# module_S-RX28_rev06_644.net
KiCad netlist of a schematic drawn in EAGLE
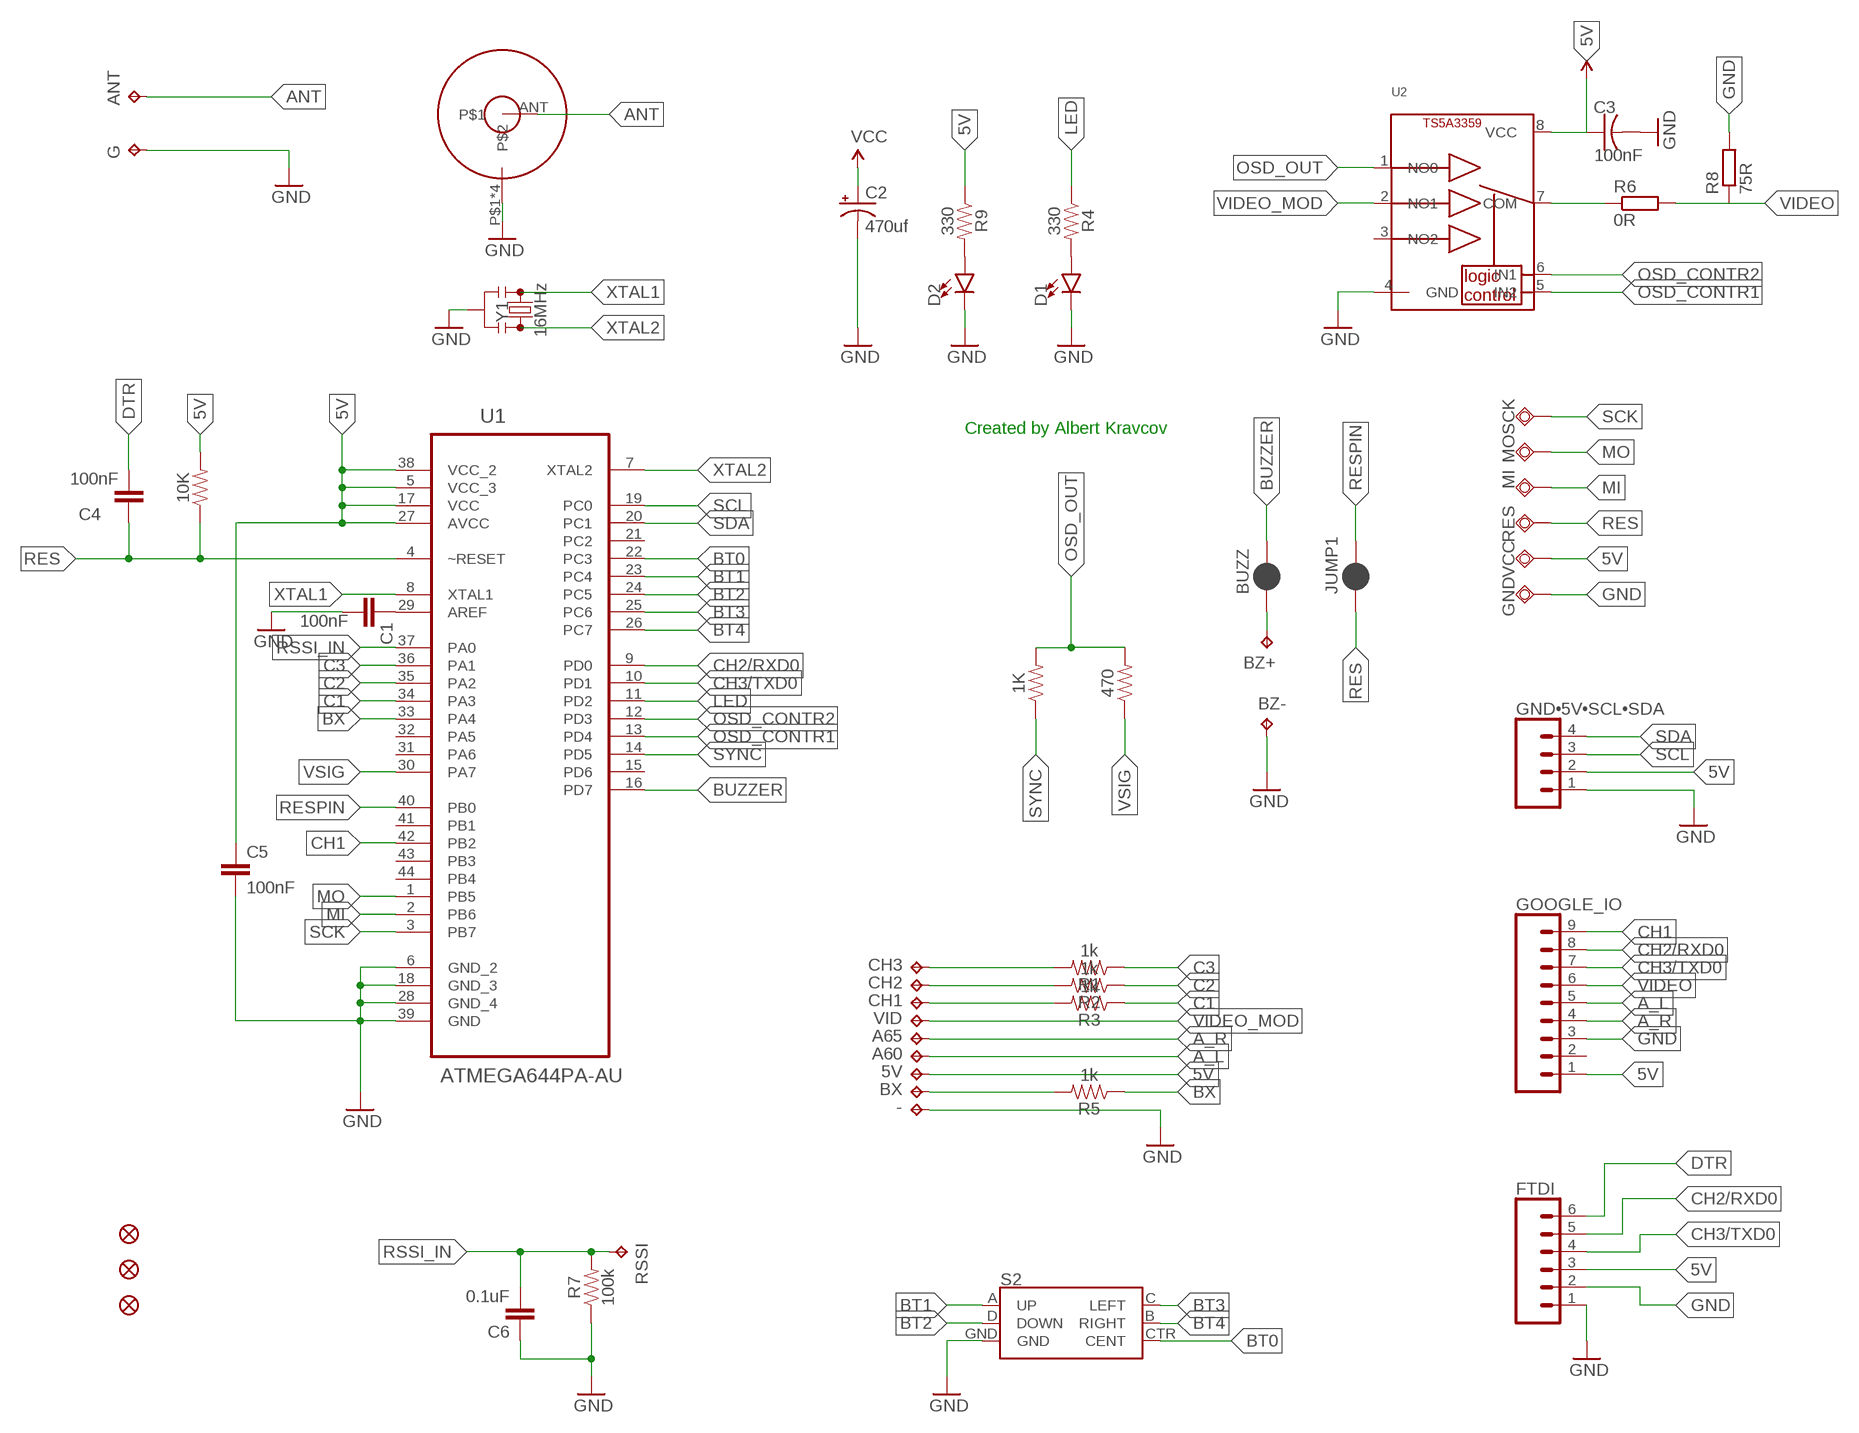
[diagram p0: schematic, sheet 1]

(export (version "E")
  (design (tool "Eeschema 10.0.6"))
  (components
    (comp (ref "-")
      (value "TPTP15SQ")
      (footprint "eagle-import:TP15SQ")
      (libsource (lib "eagle-import") (part "TPTP15SQ"))
    )
    (comp (ref "1K")
      (value "0.27OHM-0603-1/10W-1%")
      (footprint "eagle-import:0603")
      (libsource (lib "eagle-import") (part "0.27OHM-0603-1/10W-1%"))
    )
    (comp (ref "5V")
      (value "TPTP15SQ")
      (footprint "eagle-import:TP15SQ")
      (libsource (lib "eagle-import") (part "TPTP15SQ"))
    )
    (comp (ref "10K")
      (value "0.27OHM-0603-1/10W-1%")
      (footprint "eagle-import:0603")
      (libsource (lib "eagle-import") (part "0.27OHM-0603-1/10W-1%"))
    )
    (comp (ref "470")
      (value "0.27OHM-0603-1/10W-1%")
      (footprint "eagle-import:0603")
      (libsource (lib "eagle-import") (part "0.27OHM-0603-1/10W-1%"))
    )
    (comp (ref "A60")
      (value "TPTP15SQ")
      (footprint "eagle-import:TP15SQ")
      (libsource (lib "eagle-import") (part "TPTP15SQ"))
    )
    (comp (ref "A65")
      (value "TPTP15SQ")
      (footprint "eagle-import:TP15SQ")
      (libsource (lib "eagle-import") (part "TPTP15SQ"))
    )
    (comp (ref "ANT")
      (value "TPTP15R")
      (footprint "eagle-import:TP15R")
      (libsource (lib "eagle-import") (part "TPTP15R"))
    )
    (comp (ref "BUZZ")
      (value "JUMPER-SMT_2_NC_PASTE_SILK")
      (footprint "eagle-import:SMT-JUMPER_2_NC_PASTE_SILK")
      (libsource (lib "eagle-import") (part "JUMPER-SMT_2_NC_PASTE_SILK"))
    )
    (comp (ref "BX")
      (value "TPTP15SQ")
      (footprint "eagle-import:TP15SQ")
      (libsource (lib "eagle-import") (part "TPTP15SQ"))
    )
    (comp (ref "BZ+")
      (value "TPTP17SQ")
      (footprint "eagle-import:TP17SQ")
      (libsource (lib "eagle-import") (part "TPTP17SQ"))
    )
    (comp (ref "BZ-")
      (value "TPTP17SQ")
      (footprint "eagle-import:TP17SQ")
      (libsource (lib "eagle-import") (part "TPTP17SQ"))
    )
    (comp (ref "C1")
      (value "100nF")
      (footprint "eagle-import:0603")
      (libsource (lib "eagle-import") (part "10NF-0603-50V-10%"))
    )
    (comp (ref "C2")
      (value "470uf")
      (footprint "eagle-import:EIA7343")
      (libsource (lib "eagle-import") (part "CAP_POL7343"))
    )
    (comp (ref "C3")
      (value "100nF")
      (footprint "eagle-import:C0603")
      (libsource (lib "eagle-import") (part "C-USC0603"))
    )
    (comp (ref "C4")
      (value "100nF")
      (footprint "eagle-import:0603")
      (libsource (lib "eagle-import") (part "10NF-0603-50V-10%"))
    )
    (comp (ref "C5")
      (value "100nF")
      (footprint "eagle-import:0603")
      (libsource (lib "eagle-import") (part "10NF-0603-50V-10%"))
    )
    (comp (ref "C6")
      (value "0.1uF")
      (footprint "eagle-import:0603")
      (libsource (lib "eagle-import") (part "10NF-0603-50V-10%"))
    )
    (comp (ref "CH1")
      (value "TPTP15SQ")
      (footprint "eagle-import:TP15SQ")
      (libsource (lib "eagle-import") (part "TPTP15SQ"))
    )
    (comp (ref "CH2")
      (value "TPTP15SQ")
      (footprint "eagle-import:TP15SQ")
      (libsource (lib "eagle-import") (part "TPTP15SQ"))
    )
    (comp (ref "CH3")
      (value "TPTP15SQ")
      (footprint "eagle-import:TP15SQ")
      (libsource (lib "eagle-import") (part "TPTP15SQ"))
    )
    (comp (ref "D1")
      (value "LED0603")
      (footprint "eagle-import:LED-0603")
      (libsource (lib "eagle-import") (part "LED0603"))
    )
    (comp (ref "D2")
      (value "LED0603")
      (footprint "eagle-import:LED-0603")
      (libsource (lib "eagle-import") (part "LED0603"))
    )
    (comp (ref "FTDI")
      (value "CONN_06SMD-1MM")
      (footprint "eagle-import:1X06-1MM")
      (libsource (lib "eagle-import") (part "CONN_06SMD-1MM"))
    )
    (comp (ref "G")
      (value "TPTP15SQ")
      (footprint "eagle-import:TP15SQ")
      (libsource (lib "eagle-import") (part "TPTP15SQ"))
    )
    (comp (ref "GND")
      (value "GND")
      (footprint "eagle-import:B1,27")
      (libsource (lib "eagle-import") (part "TPSQB1,27"))
    )
    (comp (ref "GND•5V•SCL•SDA")
      (value "CONN_04")
      (footprint "eagle-import:1X04")
      (libsource (lib "eagle-import") (part "CONN_04"))
    )
    (comp (ref "GOOGLE_IO")
      (value "CONN_09")
      (footprint "eagle-import:1X09")
      (libsource (lib "eagle-import") (part "CONN_09"))
    )
    (comp (ref "JUMP1")
      (value "JUMPER-SMT_2_NC_PASTE_SILK")
      (footprint "eagle-import:SMT-JUMPER_2_NC_PASTE_SILK")
      (libsource (lib "eagle-import") (part "JUMPER-SMT_2_NC_PASTE_SILK"))
    )
    (comp (ref "MI")
      (value "TPSQB1,27")
      (footprint "eagle-import:B1,27")
      (libsource (lib "eagle-import") (part "TPSQB1,27"))
    )
    (comp (ref "MO")
      (value "TPSQB1,27")
      (footprint "eagle-import:B1,27")
      (libsource (lib "eagle-import") (part "TPSQB1,27"))
    )
    (comp (ref "R1")
      (value "1k")
      (footprint "eagle-import:0603")
      (libsource (lib "eagle-import") (part "0.05OHM-0603-1/5W-1%"))
    )
    (comp (ref "R2")
      (value "1k")
      (footprint "eagle-import:0603")
      (libsource (lib "eagle-import") (part "0.05OHM-0603-1/5W-1%"))
    )
    (comp (ref "R3")
      (value "1k")
      (footprint "eagle-import:0603")
      (libsource (lib "eagle-import") (part "0.05OHM-0603-1/5W-1%"))
    )
    (comp (ref "R4")
      (value "330")
      (footprint "eagle-import:0603")
      (libsource (lib "eagle-import") (part "0.05OHM-0603-1/5W-1%"))
    )
    (comp (ref "R5")
      (value "1k")
      (footprint "eagle-import:0603")
      (libsource (lib "eagle-import") (part "0.05OHM-0603-1/5W-1%"))
    )
    (comp (ref "R6")
      (value "0R")
      (footprint "eagle-import:R0603")
      (libsource (lib "eagle-import") (part "R-EU_R0603"))
    )
    (comp (ref "R7")
      (value "100k")
      (footprint "eagle-import:0603")
      (libsource (lib "eagle-import") (part "0.05OHM-0603-1/5W-1%"))
    )
    (comp (ref "R8")
      (value "75R")
      (footprint "eagle-import:R0603")
      (libsource (lib "eagle-import") (part "R-EU_R0603"))
    )
    (comp (ref "R9")
      (value "330")
      (footprint "eagle-import:0603")
      (libsource (lib "eagle-import") (part "0.05OHM-0603-1/5W-1%"))
    )
    (comp (ref "RES")
      (value "TPSQB1,27")
      (footprint "eagle-import:B1,27")
      (libsource (lib "eagle-import") (part "TPSQB1,27"))
    )
    (comp (ref "RSSI")
      (value "TPTP15SQ")
      (footprint "eagle-import:TP15SQ")
      (libsource (lib "eagle-import") (part "TPTP15SQ"))
    )
    (comp (ref "S2")
      (value "JOYSTICK_MINI")
      (footprint "eagle-import:JOYSTICK_MINI")
      (libsource (lib "eagle-import") (part "JOYSTICK_MINI"))
    )
    (comp (ref "SCK")
      (value "TPSQB1,27")
      (footprint "eagle-import:B1,27")
      (libsource (lib "eagle-import") (part "TPSQB1,27"))
    )
    (comp (ref "U$1")
      (value "SMA_ANTENNA")
      (footprint "eagle-import:SMA_CONNECTOR")
      (libsource (lib "eagle-import") (part "SMA_ANTENNA"))
    )
    (comp (ref "U$3")
      (value "FIDUCIALUFIDUCIAL")
      (footprint "eagle-import:FIDUCIAL-MICRO")
      (libsource (lib "eagle-import") (part "FIDUCIALUFIDUCIAL"))
    )
    (comp (ref "U$4")
      (value "FIDUCIALUFIDUCIAL")
      (footprint "eagle-import:FIDUCIAL-MICRO")
      (libsource (lib "eagle-import") (part "FIDUCIALUFIDUCIAL"))
    )
    (comp (ref "U$5")
      (value "FIDUCIALUFIDUCIAL")
      (footprint "eagle-import:FIDUCIAL-MICRO")
      (libsource (lib "eagle-import") (part "FIDUCIALUFIDUCIAL"))
    )
    (comp (ref "U1")
      (value "ATMEGA644PA-AU")
      (footprint "eagle-import:QFP80P1200X1200X120-44N")
      (fields (field (name "MF") "Microchip"))
      (libsource (lib "eagle-import") (part "ATMEGA644PA-AU"))
    )
    (comp (ref "U2")
      (value "TS5A3359")
      (footprint "eagle-import:VFSOP-8")
      (libsource (lib "eagle-import") (part "TS5A3359"))
    )
    (comp (ref "VCC")
      (value "TPSQB1,27")
      (footprint "eagle-import:B1,27")
      (libsource (lib "eagle-import") (part "TPSQB1,27"))
    )
    (comp (ref "VID")
      (value "TPTP15SQ")
      (footprint "eagle-import:TP15SQ")
      (libsource (lib "eagle-import") (part "TPTP15SQ"))
    )
    (comp (ref "Y1")
      (value "16MHz")
      (footprint "eagle-import:RESONATOR-SMD-3.2X1.3")
      (libsource (lib "eagle-import") (part "RESONATOR-16MHZSMD_3.2X1.3"))
    )
  )
  (nets
    (net (code "1") (name "5V") (class "Default")
      (node (ref "10K") (pin "2") (pinfunction "2_2") (pintype "passive"))
      (node (ref "5V") (pin "TP") (pinfunction "TP_TP") (pintype "input"))
      (node (ref "C2") (pin "A") (pinfunction "+_A") (pintype "passive"))
      (node (ref "C3") (pin "1") (pinfunction "1_1") (pintype "passive"))
      (node (ref "C5") (pin "1") (pinfunction "1_1") (pintype "passive"))
      (node (ref "FTDI") (pin "3") (pinfunction "3_3") (pintype "passive"))
      (node (ref "GND•5V•SCL•SDA") (pin "2") (pinfunction "2_2") (pintype "passive"))
      (node (ref "GOOGLE_IO") (pin "1") (pinfunction "1_1") (pintype "passive"))
      (node (ref "R9") (pin "1") (pinfunction "1_1") (pintype "passive"))
      (node (ref "U1") (pin "17") (pinfunction "VCC_17") (pintype "power_in"))
      (node (ref "U1") (pin "27") (pinfunction "AVCC_27") (pintype "power_in"))
      (node (ref "U1") (pin "38") (pinfunction "VCC_2_38") (pintype "power_in"))
      (node (ref "U1") (pin "5") (pinfunction "VCC_3_5") (pintype "power_in"))
      (node (ref "U2") (pin "8") (pinfunction "VCC_8") (pintype "power_in"))
      (node (ref "VCC") (pin "TP") (pinfunction "TP_TP") (pintype "input"))
    )
    (net (code "2") (name "ANT") (class "Default")
      (node (ref "ANT") (pin "TP") (pinfunction "TP_TP") (pintype "input"))
      (node (ref "U$1") (pin "ANT") (pinfunction "P$1_ANT") (pintype "bidirectional"))
    )
    (net (code "3") (name "A_L") (class "Default")
      (node (ref "A60") (pin "TP") (pinfunction "TP_TP") (pintype "input"))
      (node (ref "GOOGLE_IO") (pin "5") (pinfunction "5_5") (pintype "passive"))
    )
    (net (code "4") (name "A_R") (class "Default")
      (node (ref "A65") (pin "TP") (pinfunction "TP_TP") (pintype "input"))
      (node (ref "GOOGLE_IO") (pin "4") (pinfunction "4_4") (pintype "passive"))
    )
    (net (code "5") (name "BT0") (class "Default")
      (node (ref "S2") (pin "CTR") (pinfunction "CENT_CTR") (pintype "bidirectional"))
      (node (ref "U1") (pin "22") (pinfunction "PC3_22") (pintype "bidirectional"))
    )
    (net (code "6") (name "BT1") (class "Default")
      (node (ref "S2") (pin "A") (pinfunction "UP_A") (pintype "bidirectional"))
      (node (ref "U1") (pin "23") (pinfunction "PC4_23") (pintype "bidirectional"))
    )
    (net (code "7") (name "BT2") (class "Default")
      (node (ref "S2") (pin "D") (pinfunction "DOWN_D") (pintype "bidirectional"))
      (node (ref "U1") (pin "24") (pinfunction "PC5_24") (pintype "bidirectional"))
    )
    (net (code "8") (name "BT3") (class "Default")
      (node (ref "S2") (pin "C") (pinfunction "LEFT_C") (pintype "bidirectional"))
      (node (ref "U1") (pin "25") (pinfunction "PC6_25") (pintype "bidirectional"))
    )
    (net (code "9") (name "BT4") (class "Default")
      (node (ref "S2") (pin "B") (pinfunction "RIGHT_B") (pintype "bidirectional"))
      (node (ref "U1") (pin "26") (pinfunction "PC7_26") (pintype "bidirectional"))
    )
    (net (code "10") (name "BUZZER") (class "Default")
      (node (ref "BUZZ") (pin "2") (pinfunction "2_2") (pintype "passive"))
      (node (ref "U1") (pin "16") (pinfunction "PD7_16") (pintype "bidirectional"))
    )
    (net (code "11") (name "BX") (class "Default")
      (node (ref "R5") (pin "1") (pinfunction "1_1") (pintype "passive"))
      (node (ref "U1") (pin "33") (pinfunction "PA4_33") (pintype "bidirectional"))
    )
    (net (code "12") (name "C1") (class "Default")
      (node (ref "R3") (pin "1") (pinfunction "1_1") (pintype "passive"))
      (node (ref "U1") (pin "34") (pinfunction "PA3_34") (pintype "bidirectional"))
    )
    (net (code "13") (name "C2") (class "Default")
      (node (ref "R2") (pin "1") (pinfunction "1_1") (pintype "passive"))
      (node (ref "U1") (pin "35") (pinfunction "PA2_35") (pintype "bidirectional"))
    )
    (net (code "14") (name "C3") (class "Default")
      (node (ref "R1") (pin "1") (pinfunction "1_1") (pintype "passive"))
      (node (ref "U1") (pin "36") (pinfunction "PA1_36") (pintype "bidirectional"))
    )
    (net (code "15") (name "CH1") (class "Default")
      (node (ref "GOOGLE_IO") (pin "9") (pinfunction "9_9") (pintype "passive"))
      (node (ref "U1") (pin "42") (pinfunction "PB2_42") (pintype "bidirectional"))
    )
    (net (code "16") (name "CH2{slash}RXD0") (class "Default")
      (node (ref "FTDI") (pin "5") (pinfunction "5_5") (pintype "passive"))
      (node (ref "GOOGLE_IO") (pin "8") (pinfunction "8_8") (pintype "passive"))
      (node (ref "U1") (pin "9") (pinfunction "PD0_9") (pintype "bidirectional"))
    )
    (net (code "17") (name "CH3{slash}TXD0") (class "Default")
      (node (ref "FTDI") (pin "4") (pinfunction "4_4") (pintype "passive"))
      (node (ref "GOOGLE_IO") (pin "7") (pinfunction "7_7") (pintype "passive"))
      (node (ref "U1") (pin "10") (pinfunction "PD1_10") (pintype "bidirectional"))
    )
    (net (code "18") (name "DTR") (class "Default")
      (node (ref "C4") (pin "2") (pinfunction "2_2") (pintype "passive"))
      (node (ref "FTDI") (pin "6") (pinfunction "6_6") (pintype "passive"))
    )
    (net (code "19") (name "GND") (class "Default")
      (node (ref "-") (pin "TP") (pinfunction "TP_TP") (pintype "input"))
      (node (ref "BZ-") (pin "TP") (pinfunction "TP_TP") (pintype "input"))
      (node (ref "C1") (pin "2") (pinfunction "2_2") (pintype "passive"))
      (node (ref "C2") (pin "C") (pinfunction "-_C") (pintype "passive"))
      (node (ref "C3") (pin "2") (pinfunction "2_2") (pintype "passive"))
      (node (ref "C5") (pin "2") (pinfunction "2_2") (pintype "passive"))
      (node (ref "C6") (pin "1") (pinfunction "1_1") (pintype "passive"))
      (node (ref "D1") (pin "C") (pinfunction "C_C") (pintype "passive"))
      (node (ref "D2") (pin "C") (pinfunction "C_C") (pintype "passive"))
      (node (ref "FTDI") (pin "1") (pinfunction "1_1") (pintype "passive"))
      (node (ref "FTDI") (pin "2") (pinfunction "2_2") (pintype "passive"))
      (node (ref "G") (pin "TP") (pinfunction "TP_TP") (pintype "input"))
      (node (ref "GND") (pin "TP") (pinfunction "TP_TP") (pintype "input"))
      (node (ref "GND•5V•SCL•SDA") (pin "1") (pinfunction "1_1") (pintype "passive"))
      (node (ref "GOOGLE_IO") (pin "3") (pinfunction "3_3") (pintype "passive"))
      (node (ref "R7") (pin "1") (pinfunction "1_1") (pintype "passive"))
      (node (ref "R8") (pin "2") (pinfunction "2_2") (pintype "passive"))
      (node (ref "S2") (pin "GND") (pinfunction "GND_GND") (pintype "bidirectional"))
      (node (ref "U$1") (pin "P$1") (pinfunction "P$2_P$1") (pintype "bidirectional"))
      (node (ref "U$1") (pin "P$2") (pinfunction "P$2_P$2") (pintype "bidirectional"))
      (node (ref "U$1") (pin "P$3") (pinfunction "P$2_P$3") (pintype "bidirectional"))
      (node (ref "U$1") (pin "P$4") (pinfunction "P$2_P$4") (pintype "bidirectional"))
      (node (ref "U1") (pin "18") (pinfunction "GND_3_18") (pintype "passive"))
      (node (ref "U1") (pin "28") (pinfunction "GND_4_28") (pintype "passive"))
      (node (ref "U1") (pin "39") (pinfunction "GND_39") (pintype "passive"))
      (node (ref "U1") (pin "6") (pinfunction "GND_2_6") (pintype "passive"))
      (node (ref "U2") (pin "4") (pinfunction "GND_4") (pintype "power_in"))
      (node (ref "Y1") (pin "2") (pinfunction "2_2") (pintype "passive"))
    )
    (net (code "20") (name "LED") (class "Default")
      (node (ref "R4") (pin "1") (pinfunction "1_1") (pintype "passive"))
      (node (ref "U1") (pin "11") (pinfunction "PD2_11") (pintype "bidirectional"))
    )
    (net (code "21") (name "MI") (class "Default")
      (node (ref "MI") (pin "TP") (pinfunction "TP_TP") (pintype "input"))
      (node (ref "U1") (pin "2") (pinfunction "PB6_2") (pintype "bidirectional"))
    )
    (net (code "22") (name "MO") (class "Default")
      (node (ref "MO") (pin "TP") (pinfunction "TP_TP") (pintype "input"))
      (node (ref "U1") (pin "1") (pinfunction "PB5_1") (pintype "bidirectional"))
    )
    (net (code "23") (name "Net-(BUZZ-Pad1)") (class "Default")
      (node (ref "BUZZ") (pin "1") (pinfunction "1_1") (pintype "passive"))
      (node (ref "BZ+") (pin "TP") (pinfunction "TP_TP") (pintype "input"))
    )
    (net (code "24") (name "Net-(BX-PadTP)") (class "Default")
      (node (ref "BX") (pin "TP") (pinfunction "TP_TP") (pintype "input"))
      (node (ref "R5") (pin "2") (pinfunction "2_2") (pintype "passive"))
    )
    (net (code "25") (name "Net-(CH1-PadTP)") (class "Default")
      (node (ref "CH1") (pin "TP") (pinfunction "TP_TP") (pintype "input"))
      (node (ref "R3") (pin "2") (pinfunction "2_2") (pintype "passive"))
    )
    (net (code "26") (name "Net-(CH2-PadTP)") (class "Default")
      (node (ref "CH2") (pin "TP") (pinfunction "TP_TP") (pintype "input"))
      (node (ref "R2") (pin "2") (pinfunction "2_2") (pintype "passive"))
    )
    (net (code "27") (name "Net-(CH3-PadTP)") (class "Default")
      (node (ref "CH3") (pin "TP") (pinfunction "TP_TP") (pintype "input"))
      (node (ref "R1") (pin "2") (pinfunction "2_2") (pintype "passive"))
    )
    (net (code "28") (name "Net-(D1-PadA)") (class "Default")
      (node (ref "D1") (pin "A") (pinfunction "A_A") (pintype "passive"))
      (node (ref "R4") (pin "2") (pinfunction "2_2") (pintype "passive"))
    )
    (net (code "29") (name "Net-(D2-PadA)") (class "Default")
      (node (ref "D2") (pin "A") (pinfunction "A_A") (pintype "passive"))
      (node (ref "R9") (pin "2") (pinfunction "2_2") (pintype "passive"))
    )
    (net (code "30") (name "Net-(U1-AREF)") (class "Default")
      (node (ref "C1") (pin "1") (pinfunction "1_1") (pintype "passive"))
      (node (ref "U1") (pin "29") (pinfunction "AREF_29") (pintype "input"))
    )
    (net (code "31") (name "Net-(U2-COM)") (class "Default")
      (node (ref "R6") (pin "1") (pinfunction "1_1") (pintype "passive"))
      (node (ref "U2") (pin "7") (pinfunction "COM_7") (pintype "input"))
    )
    (net (code "32") (name "OSD_CONTR1") (class "Default")
      (node (ref "U1") (pin "13") (pinfunction "PD4_13") (pintype "bidirectional"))
      (node (ref "U2") (pin "5") (pinfunction "IN2_5") (pintype "output"))
    )
    (net (code "33") (name "OSD_CONTR2") (class "Default")
      (node (ref "U1") (pin "12") (pinfunction "PD3_12") (pintype "bidirectional"))
      (node (ref "U2") (pin "6") (pinfunction "IN1_6") (pintype "output"))
    )
    (net (code "34") (name "OSD_OUT") (class "Default")
      (node (ref "1K") (pin "2") (pinfunction "2_2") (pintype "passive"))
      (node (ref "470") (pin "2") (pinfunction "2_2") (pintype "passive"))
      (node (ref "U2") (pin "1") (pinfunction "NO0_1") (pintype "input"))
    )
    (net (code "35") (name "RES") (class "Default")
      (node (ref "10K") (pin "1") (pinfunction "1_1") (pintype "passive"))
      (node (ref "C4") (pin "1") (pinfunction "1_1") (pintype "passive"))
      (node (ref "JUMP1") (pin "1") (pinfunction "1_1") (pintype "passive"))
      (node (ref "RES") (pin "TP") (pinfunction "TP_TP") (pintype "input"))
      (node (ref "U1") (pin "4") (pinfunction "~{RESET}_4") (pintype "input"))
    )
    (net (code "36") (name "RESPIN") (class "Default")
      (node (ref "JUMP1") (pin "2") (pinfunction "2_2") (pintype "passive"))
      (node (ref "U1") (pin "40") (pinfunction "PB0_40") (pintype "bidirectional"))
    )
    (net (code "37") (name "RSSI_IN") (class "Default")
      (node (ref "C6") (pin "2") (pinfunction "2_2") (pintype "passive"))
      (node (ref "R7") (pin "2") (pinfunction "2_2") (pintype "passive"))
      (node (ref "RSSI") (pin "TP") (pinfunction "TP_TP") (pintype "input"))
      (node (ref "U1") (pin "37") (pinfunction "PA0_37") (pintype "bidirectional"))
    )
    (net (code "38") (name "SCK") (class "Default")
      (node (ref "SCK") (pin "TP") (pinfunction "TP_TP") (pintype "input"))
      (node (ref "U1") (pin "3") (pinfunction "PB7_3") (pintype "bidirectional"))
    )
    (net (code "39") (name "SCL") (class "Default")
      (node (ref "GND•5V•SCL•SDA") (pin "3") (pinfunction "3_3") (pintype "passive"))
      (node (ref "U1") (pin "19") (pinfunction "PC0_19") (pintype "bidirectional"))
    )
    (net (code "40") (name "SDA") (class "Default")
      (node (ref "GND•5V•SCL•SDA") (pin "4") (pinfunction "4_4") (pintype "passive"))
      (node (ref "U1") (pin "20") (pinfunction "PC1_20") (pintype "bidirectional"))
    )
    (net (code "41") (name "SYNC") (class "Default")
      (node (ref "1K") (pin "1") (pinfunction "1_1") (pintype "passive"))
      (node (ref "U1") (pin "14") (pinfunction "PD5_14") (pintype "bidirectional"))
    )
    (net (code "42") (name "VIDEO") (class "Default")
      (node (ref "GOOGLE_IO") (pin "6") (pinfunction "6_6") (pintype "passive"))
      (node (ref "R6") (pin "2") (pinfunction "2_2") (pintype "passive"))
      (node (ref "R8") (pin "1") (pinfunction "1_1") (pintype "passive"))
    )
    (net (code "43") (name "VIDEO_MOD") (class "Default")
      (node (ref "U2") (pin "2") (pinfunction "NO1_2") (pintype "input"))
      (node (ref "VID") (pin "TP") (pinfunction "TP_TP") (pintype "input"))
    )
    (net (code "44") (name "VSIG") (class "Default")
      (node (ref "470") (pin "1") (pinfunction "1_1") (pintype "passive"))
      (node (ref "U1") (pin "30") (pinfunction "PA7_30") (pintype "bidirectional"))
    )
    (net (code "45") (name "XTAL1") (class "Default")
      (node (ref "U1") (pin "8") (pinfunction "XTAL1_8") (pintype "input"))
      (node (ref "Y1") (pin "1") (pinfunction "1_1") (pintype "passive"))
    )
    (net (code "46") (name "XTAL2") (class "Default")
      (node (ref "U1") (pin "7") (pinfunction "XTAL2_7") (pintype "output"))
      (node (ref "Y1") (pin "3") (pinfunction "3_3") (pintype "passive"))
    )
    (net (code "47") (name "unconnected-(GOOGLE_IO-Pad2)") (class "Default")
      (node (ref "GOOGLE_IO") (pin "2") (pinfunction "2_2") (pintype "passive"))
    )
    (net (code "48") (name "unconnected-(U1-PA5-Pad32)") (class "Default")
      (node (ref "U1") (pin "32") (pinfunction "PA5_32") (pintype "bidirectional"))
    )
    (net (code "49") (name "unconnected-(U1-PA6-Pad31)") (class "Default")
      (node (ref "U1") (pin "31") (pinfunction "PA6_31") (pintype "bidirectional"))
    )
    (net (code "50") (name "unconnected-(U1-PB1-Pad41)") (class "Default")
      (node (ref "U1") (pin "41") (pinfunction "PB1_41") (pintype "bidirectional"))
    )
    (net (code "51") (name "unconnected-(U1-PB3-Pad43)") (class "Default")
      (node (ref "U1") (pin "43") (pinfunction "PB3_43") (pintype "bidirectional"))
    )
    (net (code "52") (name "unconnected-(U1-PB4-Pad44)") (class "Default")
      (node (ref "U1") (pin "44") (pinfunction "PB4_44") (pintype "bidirectional"))
    )
    (net (code "53") (name "unconnected-(U1-PC2-Pad21)") (class "Default")
      (node (ref "U1") (pin "21") (pinfunction "PC2_21") (pintype "bidirectional"))
    )
    (net (code "54") (name "unconnected-(U1-PD6-Pad15)") (class "Default")
      (node (ref "U1") (pin "15") (pinfunction "PD6_15") (pintype "bidirectional"))
    )
    (net (code "55") (name "unconnected-(U2-NO2-Pad3)") (class "Default")
      (node (ref "U2") (pin "3") (pinfunction "NO2_3") (pintype "input"))
    )
  )
)
